# BUZZER.net
KiCad netlist of a schematic drawn in Altium Designer
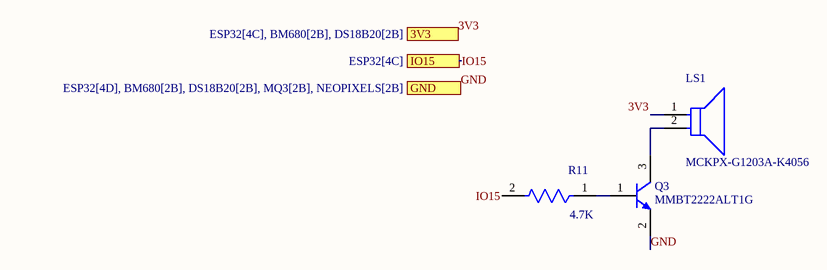
[diagram p0: BUZZER.SchDoc]

(export (version "E")
  (design (tool "Eeschema 10.0.6"))
  (components
    (comp (ref "LS1")
      (value "MCKPX-G1203A-K4056")
      (footprint "FP-MCKPX-G1203A-K4056-MFG")
      (description "MAGNETIC BUZZER AND TRANSDUCER - More Details")
      (fields
        (field (name "MANUFACTURER") "Multicomp Pro")
        (field (name "OCTOPART") "https://octopart.com/mckpx-g1203a-k4056-multicomp-12157154")
      )
      (libsource (lib "Altium Content Vault") (part "1973c4b650225fd2ddacaff6b763965"))
    )
    (comp (ref "Q3")
      (value "MMBT2222ALT1G")
      (footprint "ONSC-SOT-23-3-318-08_V")
      (description "General Purpose Transistor, NPN Silicon, 3-Pin SOT-23, Pb-Free, Tape and Reel")
      (fields (field (name "MANUFACTURER") "On Semiconductor"))
      (libsource (lib "Altium Content Vault") (part "ONSC-NPN-B1E2C3-3"))
    )
    (comp (ref "R11")
      (value "4.7K")
      (footprint "FP-ERA6A-IPC_B")
      (description "RES 100K OHM 0.1% 1/8W 0805")
      (fields (field (name "TOLERANCE") "0.1%"))
      (libsource (lib "Altium Content Vault") (part "1029c3af85768c4190bb7ad29bc67b5"))
    )
  )
  (nets
    (net (code "1") (name "/3V3") (class "Default")
      (node (ref "LS1") (pin "1") (pinfunction "C_1") (pintype "passive"))
    )
    (net (code "2") (name "/GND") (class "Default")
      (node (ref "Q3") (pin "2") (pinfunction "E_2") (pintype "passive"))
    )
    (net (code "3") (name "/IO15") (class "Default")
      (node (ref "R11") (pin "2") (pinfunction "2_2") (pintype "passive"))
    )
    (net (code "4") (name "Net-(LS1-A)") (class "Default")
      (node (ref "LS1") (pin "2") (pinfunction "A_2") (pintype "passive"))
      (node (ref "Q3") (pin "3") (pinfunction "C_3") (pintype "passive"))
    )
    (net (code "5") (name "Net-(Q3-B)") (class "Default")
      (node (ref "Q3") (pin "1") (pinfunction "B_1") (pintype "passive"))
      (node (ref "R11") (pin "1") (pinfunction "1_1") (pintype "passive"))
    )
  )
)
